# FMC_HPC1.net
KiCad netlist of a schematic drawn in Altium Designer
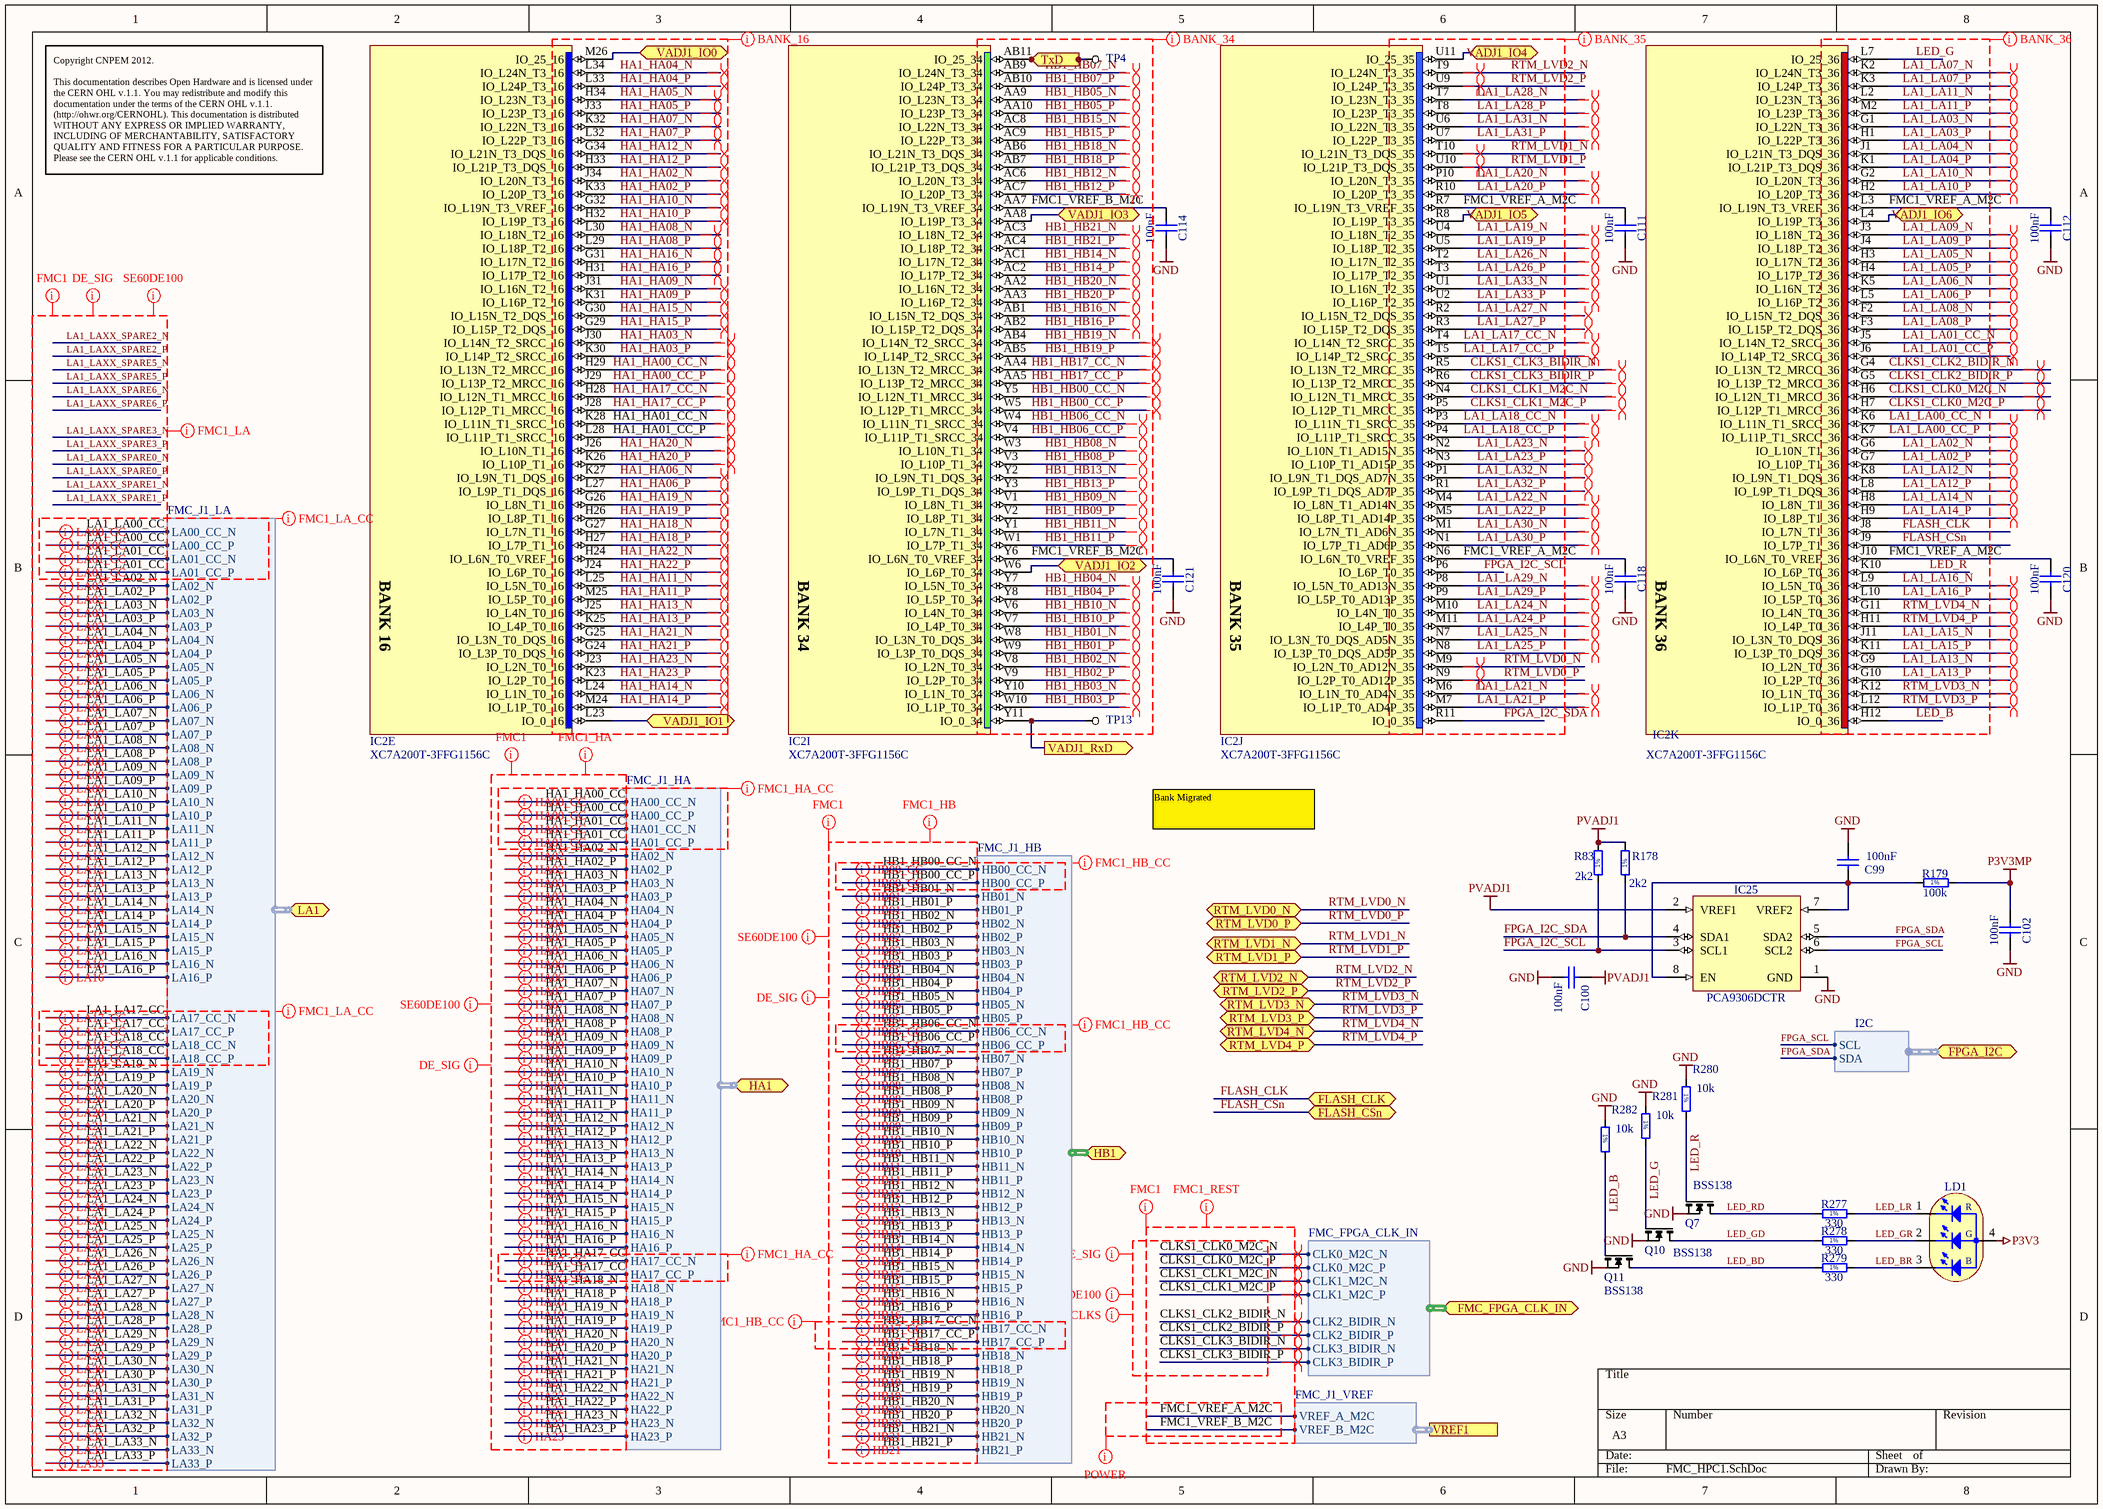
[diagram p0: FMC_HPC1.SchDoc]

(export (version "E")
  (design (tool "Eeschema 10.0.6"))
  (components
    (comp (ref "C99")
      (value "100nF")
      (footprint "CAPC0603X33N")
      (description "Non-polarised capacitor")
      (fields
        (field (name "PART NUMBER") "CC0201_100NF_6.3V_10%_X5R")
        (field (name "VOLTAGE") "6.3V")
        (field (name "AUTHOR") "CERN DEM JLC")
      )
      (libsource (lib "Capacitors") (part "Capacitor - non polarized"))
    )
    (comp (ref "C100")
      (value "100nF")
      (footprint "CAPC0603X33N")
      (description "Non-polarised capacitor")
      (fields
        (field (name "PART NUMBER") "CC0201_100NF_6.3V_10%_X5R")
        (field (name "VOLTAGE") "6.3V")
        (field (name "AUTHOR") "CERN DEM JLC")
      )
      (libsource (lib "Capacitors") (part "Capacitor - non polarized"))
    )
    (comp (ref "C102")
      (value "100nF")
      (footprint "CAPC0603X33N")
      (description "Non-polarised capacitor")
      (fields
        (field (name "PART NUMBER") "CC0201_100NF_6.3V_10%_X5R")
        (field (name "VOLTAGE") "6.3V")
        (field (name "AUTHOR") "CERN DEM JLC")
      )
      (libsource (lib "Capacitors") (part "Capacitor - non polarized"))
    )
    (comp (ref "C111")
      (value "100nF")
      (footprint "CAPC0603X33N")
      (description "Non-polarised capacitor")
      (fields
        (field (name "PART NUMBER") "CC0201_100NF_6.3V_10%_X5R")
        (field (name "VOLTAGE") "6.3V")
        (field (name "AUTHOR") "CERN DEM JLC")
      )
      (libsource (lib "Capacitors") (part "Capacitor - non polarized"))
    )
    (comp (ref "C112")
      (value "100nF")
      (footprint "CAPC0603X33N")
      (description "Non-polarised capacitor")
      (fields
        (field (name "PART NUMBER") "CC0201_100NF_6.3V_10%_X5R")
        (field (name "VOLTAGE") "6.3V")
        (field (name "AUTHOR") "CERN DEM JLC")
      )
      (libsource (lib "Capacitors") (part "Capacitor - non polarized"))
    )
    (comp (ref "C114")
      (value "100nF")
      (footprint "CAPC0603X33N")
      (description "Non-polarised capacitor")
      (fields
        (field (name "PART NUMBER") "CC0201_100NF_6.3V_10%_X5R")
        (field (name "VOLTAGE") "6.3V")
        (field (name "AUTHOR") "CERN DEM JLC")
      )
      (libsource (lib "Capacitors") (part "Capacitor - non polarized"))
    )
    (comp (ref "C118")
      (value "100nF")
      (footprint "CAPC0603X33N")
      (description "Non-polarised capacitor")
      (fields
        (field (name "PART NUMBER") "CC0201_100NF_6.3V_10%_X5R")
        (field (name "VOLTAGE") "6.3V")
        (field (name "AUTHOR") "CERN DEM JLC")
      )
      (libsource (lib "Capacitors") (part "Capacitor - non polarized"))
    )
    (comp (ref "C120")
      (value "100nF")
      (footprint "CAPC0603X33N")
      (description "Non-polarised capacitor")
      (fields
        (field (name "PART NUMBER") "CC0201_100NF_6.3V_10%_X5R")
        (field (name "VOLTAGE") "6.3V")
        (field (name "AUTHOR") "CERN DEM JLC")
      )
      (libsource (lib "Capacitors") (part "Capacitor - non polarized"))
    )
    (comp (ref "C121")
      (value "100nF")
      (footprint "CAPC0603X33N")
      (description "Non-polarised capacitor")
      (fields
        (field (name "PART NUMBER") "CC0201_100NF_6.3V_10%_X5R")
        (field (name "VOLTAGE") "6.3V")
        (field (name "AUTHOR") "CERN DEM JLC")
      )
      (libsource (lib "Capacitors") (part "Capacitor - non polarized"))
    )
    (comp (ref "IC2")
      (value "XC7A200T-3FFG1156C")
      (footprint "BGA1156C100P34X34_3500X3500X335")
      (description "Artix-6 FPGA, 16 GTPs, 600 User I/Os, 1156-Pin BGA, Speed Grade 2, Commercial Grade, Pb-Free")
      (fields (field (name "MANUFACTURER") "XILINX") (field (name "AUTHOR") "CERN DEM JLC"))
      (libsource (lib "AMC_FMC_Carrier") (part "XC7A200T-3FFG1156C"))
    )
    (comp (ref "IC25")
      (value "PCA9306DCTR")
      (footprint "SOP65P400X130-8N")
      (description "Dual Bidirectional I2C Bus And SMBus Voltage-Level Translator")
      (fields (field (name "MANUFACTURER") "TEXAS INSTRUMENTS") (field (name "AUTHOR") "CERN DEM JLC"))
      (libsource (lib "ICs And Semiconductors") (part "PCA9306DC"))
    )
    (comp (ref "LD1")
      (value "Red/Green/Blue")
      (footprint "LED_OPTEK_OVSRRGBCC3_a")
      (description "Right Angle Tricolor (RGB) Surface Mount LED, Body 3.2x1mm")
      (fields
        (field (name "PART NUMBER") "LED_OPTEK_OVSRRGBCC3_a")
        (field (name "MANUFACTURER") "OPTEK / TT ELECTRONICS")
        (field (name "AUTHOR") "CERN DEM JLC")
      )
      (libsource (lib "ICs And Semiconductors") (part "LED_OPTEK_OVSRRGBCC3"))
    )
    (comp (ref "Q7")
      (value "BSS138")
      (footprint "SOT95P251X112-3N")
      (libsource (lib "LIBRARY_SCH") (part "Q_BSS138"))
    )
    (comp (ref "Q10")
      (value "BSS138")
      (footprint "SOT95P251X112-3N")
      (libsource (lib "LIBRARY_SCH") (part "Q_BSS138"))
    )
    (comp (ref "Q11")
      (value "BSS138")
      (footprint "SOT95P251X112-3N")
      (libsource (lib "LIBRARY_SCH") (part "Q_BSS138"))
    )
    (comp (ref "R83")
      (value "2k2")
      (footprint "RESC1005X40N")
      (description "Resistor - 1%")
      (fields
        (field (name "PART NUMBER") "R0402_2K2_1%_0.0625W_100PPM")
        (field (name "POWER") "0.0625W")
        (field (name "AUTHOR") "CERN DEM JLC")
      )
      (libsource (lib "Resistors") (part "Resistor - 1%"))
    )
    (comp (ref "R178")
      (value "2k2")
      (footprint "RESC1005X40N")
      (description "Resistor - 1%")
      (fields
        (field (name "PART NUMBER") "R0402_2K2_1%_0.0625W_100PPM")
        (field (name "POWER") "0.0625W")
        (field (name "AUTHOR") "CERN DEM JLC")
      )
      (libsource (lib "Resistors") (part "Resistor - 1%"))
    )
    (comp (ref "R179")
      (value "100k")
      (footprint "RESC1005X40N")
      (description "Resistor - 1%")
      (fields
        (field (name "PART NUMBER") "R0402_100K_1%_0.0625W_100PPM")
        (field (name "POWER") "0.0625W")
        (field (name "AUTHOR") "CERN DEM JLC")
      )
      (libsource (lib "Resistors") (part "Resistor - 1%"))
    )
    (comp (ref "R277")
      (value "330")
      (footprint "RESC1005X40N")
      (description "Resistor - 1%")
      (fields
        (field (name "PART NUMBER") "R0402_330R_1%_0.0625W_100PPM")
        (field (name "POWER") "0.0625W")
        (field (name "AUTHOR") "CERN DEM JLC")
      )
      (libsource (lib "Resistors") (part "Resistor - 1%"))
    )
    (comp (ref "R278")
      (value "330")
      (footprint "RESC1005X40N")
      (description "Resistor - 1%")
      (fields
        (field (name "PART NUMBER") "R0402_330R_1%_0.0625W_100PPM")
        (field (name "POWER") "0.0625W")
        (field (name "AUTHOR") "CERN DEM JLC")
      )
      (libsource (lib "Resistors") (part "Resistor - 1%"))
    )
    (comp (ref "R279")
      (value "330")
      (footprint "RESC1005X40N")
      (description "Resistor - 1%")
      (fields
        (field (name "PART NUMBER") "R0402_330R_1%_0.0625W_100PPM")
        (field (name "POWER") "0.0625W")
        (field (name "AUTHOR") "CERN DEM JLC")
      )
      (libsource (lib "Resistors") (part "Resistor - 1%"))
    )
    (comp (ref "R280")
      (value "10k")
      (footprint "RESC1005X40N")
      (description "Resistor - 1%")
      (fields
        (field (name "PART NUMBER") "R0402_10K_1%_0.0625W_100PPM")
        (field (name "POWER") "0.0625W")
        (field (name "AUTHOR") "CERN DEM JLC")
      )
      (libsource (lib "Resistors") (part "Resistor - 1%"))
    )
    (comp (ref "R281")
      (value "10k")
      (footprint "RESC1005X40N")
      (description "Resistor - 1%")
      (fields
        (field (name "PART NUMBER") "R0402_10K_1%_0.0625W_100PPM")
        (field (name "POWER") "0.0625W")
        (field (name "AUTHOR") "CERN DEM JLC")
      )
      (libsource (lib "Resistors") (part "Resistor - 1%"))
    )
    (comp (ref "R282")
      (value "10k")
      (footprint "RESC1005X40N")
      (description "Resistor - 1%")
      (fields
        (field (name "PART NUMBER") "R0402_10K_1%_0.0625W_100PPM")
        (field (name "POWER") "0.0625W")
        (field (name "AUTHOR") "CERN DEM JLC")
      )
      (libsource (lib "Resistors") (part "Resistor - 1%"))
    )
    (comp (ref "TP4")
      (value "TP")
      (footprint "TP_large")
      (description "Testpoint")
      (libsource (lib "LIBRARY_SCH") (part "TP"))
    )
    (comp (ref "TP13")
      (value "TP")
      (footprint "TP_large")
      (description "Testpoint")
      (libsource (lib "LIBRARY_SCH") (part "TP"))
    )
  )
  (nets
    (net (code "7") (name "/CLKS1_CLK0_M2C_N") (class "Default")
      (node (ref "IC2") (pin "H6") (pinfunction "IO_L12N_T1_MRCC_36_H6") (pintype "bidirectional"))
    )
    (net (code "8") (name "/CLKS1_CLK0_M2C_P") (class "Default")
      (node (ref "IC2") (pin "H7") (pinfunction "IO_L12P_T1_MRCC_36_H7") (pintype "bidirectional"))
    )
    (net (code "9") (name "/CLKS1_CLK1_M2C_N") (class "Default")
      (node (ref "IC2") (pin "N4") (pinfunction "IO_L12N_T1_MRCC_35_N4") (pintype "bidirectional"))
    )
    (net (code "10") (name "/CLKS1_CLK1_M2C_P") (class "Default")
      (node (ref "IC2") (pin "P5") (pinfunction "IO_L12P_T1_MRCC_35_P5") (pintype "bidirectional"))
    )
    (net (code "11") (name "/CLKS1_CLK2_BIDIR_N") (class "Default")
      (node (ref "IC2") (pin "G4") (pinfunction "IO_L13N_T2_MRCC_36_G4") (pintype "bidirectional"))
    )
    (net (code "12") (name "/CLKS1_CLK2_BIDIR_P") (class "Default")
      (node (ref "IC2") (pin "G5") (pinfunction "IO_L13P_T2_MRCC_36_G5") (pintype "bidirectional"))
    )
    (net (code "13") (name "/CLKS1_CLK3_BIDIR_N") (class "Default")
      (node (ref "IC2") (pin "R5") (pinfunction "IO_L13N_T2_MRCC_35_R5") (pintype "bidirectional"))
    )
    (net (code "14") (name "/CLKS1_CLK3_BIDIR_P") (class "Default")
      (node (ref "IC2") (pin "R6") (pinfunction "IO_L13P_T2_MRCC_35_R6") (pintype "bidirectional"))
    )
    (net (code "15") (name "/FLASH_CLK") (class "Default")
      (node (ref "IC2") (pin "J8") (pinfunction "IO_L7N_T1_36_J8") (pintype "bidirectional"))
    )
    (net (code "16") (name "/FLASH_CSn") (class "Default")
      (node (ref "IC2") (pin "J9") (pinfunction "IO_L7P_T1_36_J9") (pintype "bidirectional"))
    )
    (net (code "17") (name "/FMC1_VREF_A_M2C") (class "Default")
      (node (ref "C111") (pin "1") (pinfunction "1_1") (pintype "passive"))
      (node (ref "C112") (pin "1") (pinfunction "1_1") (pintype "passive"))
      (node (ref "C118") (pin "1") (pinfunction "1_1") (pintype "passive"))
      (node (ref "C120") (pin "1") (pinfunction "1_1") (pintype "passive"))
      (node (ref "IC2") (pin "J10") (pinfunction "IO_L6N_T0_VREF_36_J10") (pintype "bidirectional"))
      (node (ref "IC2") (pin "L3") (pinfunction "IO_L19N_T3_VREF_36_L3") (pintype "bidirectional"))
      (node (ref "IC2") (pin "N6") (pinfunction "IO_L6N_T0_VREF_35_N6") (pintype "bidirectional"))
      (node (ref "IC2") (pin "R7") (pinfunction "IO_L19N_T3_VREF_35_R7") (pintype "bidirectional"))
    )
    (net (code "18") (name "/FMC1_VREF_B_M2C") (class "Default")
      (node (ref "C114") (pin "1") (pinfunction "1_1") (pintype "passive"))
      (node (ref "C121") (pin "1") (pinfunction "1_1") (pintype "passive"))
      (node (ref "IC2") (pin "AA7") (pinfunction "IO_L19N_T3_VREF_34_AA7") (pintype "bidirectional"))
      (node (ref "IC2") (pin "Y6") (pinfunction "IO_L6N_T0_VREF_34_Y6") (pintype "bidirectional"))
    )
    (net (code "19") (name "/FPGA_I2C_SCL") (class "Default")
      (node (ref "IC2") (pin "P6") (pinfunction "IO_L6P_T0_35_P6") (pintype "bidirectional"))
      (node (ref "IC25") (pin "3") (pinfunction "SCL1_3") (pintype "bidirectional"))
      (node (ref "R83") (pin "1") (pinfunction "1_1") (pintype "passive"))
    )
    (net (code "20") (name "/FPGA_I2C_SDA") (class "Default")
      (node (ref "IC2") (pin "R11") (pinfunction "IO_0_35_R11") (pintype "bidirectional"))
      (node (ref "IC25") (pin "4") (pinfunction "SDA1_4") (pintype "bidirectional"))
      (node (ref "R178") (pin "1") (pinfunction "1_1") (pintype "passive"))
    )
    (net (code "21") (name "/FPGA_SCL") (class "Default")
      (node (ref "IC25") (pin "6") (pinfunction "SCL2_6") (pintype "bidirectional"))
    )
    (net (code "22") (name "/FPGA_SDA") (class "Default")
      (node (ref "IC25") (pin "5") (pinfunction "SDA2_5") (pintype "bidirectional"))
    )
    (net (code "23") (name "/HA1_HA00_CC_N") (class "Default")
      (node (ref "IC2") (pin "H29") (pinfunction "IO_L13N_T2_MRCC_16_H29") (pintype "bidirectional"))
    )
    (net (code "24") (name "/HA1_HA00_CC_P") (class "Default")
      (node (ref "IC2") (pin "J29") (pinfunction "IO_L13P_T2_MRCC_16_J29") (pintype "bidirectional"))
    )
    (net (code "25") (name "/HA1_HA01_CC_N") (class "Default")
      (node (ref "IC2") (pin "K28") (pinfunction "IO_L11N_T1_SRCC_16_K28") (pintype "bidirectional"))
    )
    (net (code "26") (name "/HA1_HA01_CC_P") (class "Default")
      (node (ref "IC2") (pin "L28") (pinfunction "IO_L11P_T1_SRCC_16_L28") (pintype "bidirectional"))
    )
    (net (code "27") (name "/HA1_HA02_N") (class "Default")
      (node (ref "IC2") (pin "J34") (pinfunction "IO_L20N_T3_16_J34") (pintype "bidirectional"))
    )
    (net (code "28") (name "/HA1_HA02_P") (class "Default")
      (node (ref "IC2") (pin "K33") (pinfunction "IO_L20P_T3_16_K33") (pintype "bidirectional"))
    )
    (net (code "29") (name "/HA1_HA03_N") (class "Default")
      (node (ref "IC2") (pin "J30") (pinfunction "IO_L14N_T2_SRCC_16_J30") (pintype "bidirectional"))
    )
    (net (code "30") (name "/HA1_HA03_P") (class "Default")
      (node (ref "IC2") (pin "K30") (pinfunction "IO_L14P_T2_SRCC_16_K30") (pintype "bidirectional"))
    )
    (net (code "31") (name "/HA1_HA04_N") (class "Default")
      (node (ref "IC2") (pin "L34") (pinfunction "IO_L24N_T3_16_L34") (pintype "bidirectional"))
    )
    (net (code "32") (name "/HA1_HA04_P") (class "Default")
      (node (ref "IC2") (pin "L33") (pinfunction "IO_L24P_T3_16_L33") (pintype "bidirectional"))
    )
    (net (code "33") (name "/HA1_HA05_N") (class "Default")
      (node (ref "IC2") (pin "H34") (pinfunction "IO_L23N_T3_16_H34") (pintype "bidirectional"))
    )
    (net (code "34") (name "/HA1_HA05_P") (class "Default")
      (node (ref "IC2") (pin "J33") (pinfunction "IO_L23P_T3_16_J33") (pintype "bidirectional"))
    )
    (net (code "35") (name "/HA1_HA06_N") (class "Default")
      (node (ref "IC2") (pin "K27") (pinfunction "IO_L9N_T1_DQS_16_K27") (pintype "bidirectional"))
    )
    (net (code "36") (name "/HA1_HA06_P") (class "Default")
      (node (ref "IC2") (pin "L27") (pinfunction "IO_L9P_T1_DQS_16_L27") (pintype "bidirectional"))
    )
    (net (code "37") (name "/HA1_HA07_N") (class "Default")
      (node (ref "IC2") (pin "K32") (pinfunction "IO_L22N_T3_16_K32") (pintype "bidirectional"))
    )
    (net (code "38") (name "/HA1_HA07_P") (class "Default")
      (node (ref "IC2") (pin "L32") (pinfunction "IO_L22P_T3_16_L32") (pintype "bidirectional"))
    )
    (net (code "39") (name "/HA1_HA08_N") (class "Default")
      (node (ref "IC2") (pin "L30") (pinfunction "IO_L18N_T2_16_L30") (pintype "bidirectional"))
    )
    (net (code "40") (name "/HA1_HA08_P") (class "Default")
      (node (ref "IC2") (pin "L29") (pinfunction "IO_L18P_T2_16_L29") (pintype "bidirectional"))
    )
    (net (code "41") (name "/HA1_HA09_N") (class "Default")
      (node (ref "IC2") (pin "J31") (pinfunction "IO_L16N_T2_16_J31") (pintype "bidirectional"))
    )
    (net (code "42") (name "/HA1_HA09_P") (class "Default")
      (node (ref "IC2") (pin "K31") (pinfunction "IO_L16P_T2_16_K31") (pintype "bidirectional"))
    )
    (net (code "43") (name "/HA1_HA10_N") (class "Default")
      (node (ref "IC2") (pin "G32") (pinfunction "IO_L19N_T3_VREF_16_G32") (pintype "bidirectional"))
    )
    (net (code "44") (name "/HA1_HA10_P") (class "Default")
      (node (ref "IC2") (pin "H32") (pinfunction "IO_L19P_T3_16_H32") (pintype "bidirectional"))
    )
    (net (code "45") (name "/HA1_HA11_N") (class "Default")
      (node (ref "IC2") (pin "L25") (pinfunction "IO_L5N_T0_16_L25") (pintype "bidirectional"))
    )
    (net (code "46") (name "/HA1_HA11_P") (class "Default")
      (node (ref "IC2") (pin "M25") (pinfunction "IO_L5P_T0_16_M25") (pintype "bidirectional"))
    )
    (net (code "47") (name "/HA1_HA12_N") (class "Default")
      (node (ref "IC2") (pin "G34") (pinfunction "IO_L21N_T3_DQS_16_G34") (pintype "bidirectional"))
    )
    (net (code "48") (name "/HA1_HA12_P") (class "Default")
      (node (ref "IC2") (pin "H33") (pinfunction "IO_L21P_T3_DQS_16_H33") (pintype "bidirectional"))
    )
    (net (code "49") (name "/HA1_HA13_N") (class "Default")
      (node (ref "IC2") (pin "J25") (pinfunction "IO_L4N_T0_16_J25") (pintype "bidirectional"))
    )
    (net (code "50") (name "/HA1_HA13_P") (class "Default")
      (node (ref "IC2") (pin "K25") (pinfunction "IO_L4P_T0_16_K25") (pintype "bidirectional"))
    )
    (net (code "51") (name "/HA1_HA14_N") (class "Default")
      (node (ref "IC2") (pin "L24") (pinfunction "IO_L1N_T0_16_L24") (pintype "bidirectional"))
    )
    (net (code "52") (name "/HA1_HA14_P") (class "Default")
      (node (ref "IC2") (pin "M24") (pinfunction "IO_L1P_T0_16_M24") (pintype "bidirectional"))
    )
    (net (code "53") (name "/HA1_HA15_N") (class "Default")
      (node (ref "IC2") (pin "G30") (pinfunction "IO_L15N_T2_DQS_16_G30") (pintype "bidirectional"))
    )
    (net (code "54") (name "/HA1_HA15_P") (class "Default")
      (node (ref "IC2") (pin "G29") (pinfunction "IO_L15P_T2_DQS_16_G29") (pintype "bidirectional"))
    )
    (net (code "55") (name "/HA1_HA16_N") (class "Default")
      (node (ref "IC2") (pin "G31") (pinfunction "IO_L17N_T2_16_G31") (pintype "bidirectional"))
    )
    (net (code "56") (name "/HA1_HA16_P") (class "Default")
      (node (ref "IC2") (pin "H31") (pinfunction "IO_L17P_T2_16_H31") (pintype "bidirectional"))
    )
    (net (code "57") (name "/HA1_HA17_CC_N") (class "Default")
      (node (ref "IC2") (pin "H28") (pinfunction "IO_L12N_T1_MRCC_16_H28") (pintype "bidirectional"))
    )
    (net (code "58") (name "/HA1_HA17_CC_P") (class "Default")
      (node (ref "IC2") (pin "J28") (pinfunction "IO_L12P_T1_MRCC_16_J28") (pintype "bidirectional"))
    )
    (net (code "59") (name "/HA1_HA18_N") (class "Default")
      (node (ref "IC2") (pin "G27") (pinfunction "IO_L7N_T1_16_G27") (pintype "bidirectional"))
    )
    (net (code "60") (name "/HA1_HA18_P") (class "Default")
      (node (ref "IC2") (pin "H27") (pinfunction "IO_L7P_T1_16_H27") (pintype "bidirectional"))
    )
    (net (code "61") (name "/HA1_HA19_N") (class "Default")
      (node (ref "IC2") (pin "G26") (pinfunction "IO_L8N_T1_16_G26") (pintype "bidirectional"))
    )
    (net (code "62") (name "/HA1_HA19_P") (class "Default")
      (node (ref "IC2") (pin "H26") (pinfunction "IO_L8P_T1_16_H26") (pintype "bidirectional"))
    )
    (net (code "63") (name "/HA1_HA20_N") (class "Default")
      (node (ref "IC2") (pin "J26") (pinfunction "IO_L10N_T1_16_J26") (pintype "bidirectional"))
    )
    (net (code "64") (name "/HA1_HA20_P") (class "Default")
      (node (ref "IC2") (pin "K26") (pinfunction "IO_L10P_T1_16_K26") (pintype "bidirectional"))
    )
    (net (code "65") (name "/HA1_HA21_N") (class "Default")
      (node (ref "IC2") (pin "G25") (pinfunction "IO_L3N_T0_DQS_16_G25") (pintype "bidirectional"))
    )
    (net (code "66") (name "/HA1_HA21_P") (class "Default")
      (node (ref "IC2") (pin "G24") (pinfunction "IO_L3P_T0_DQS_16_G24") (pintype "bidirectional"))
    )
    (net (code "67") (name "/HA1_HA22_N") (class "Default")
      (node (ref "IC2") (pin "H24") (pinfunction "IO_L6N_T0_VREF_16_H24") (pintype "bidirectional"))
    )
    (net (code "68") (name "/HA1_HA22_P") (class "Default")
      (node (ref "IC2") (pin "J24") (pinfunction "IO_L6P_T0_16_J24") (pintype "bidirectional"))
    )
    (net (code "69") (name "/HA1_HA23_N") (class "Default")
      (node (ref "IC2") (pin "J23") (pinfunction "IO_L2N_T0_16_J23") (pintype "bidirectional"))
    )
    (net (code "70") (name "/HA1_HA23_P") (class "Default")
      (node (ref "IC2") (pin "K23") (pinfunction "IO_L2P_T0_16_K23") (pintype "bidirectional"))
    )
    (net (code "71") (name "/HB1_HB00_CC_N") (class "Default")
      (node (ref "IC2") (pin "Y5") (pinfunction "IO_L12N_T1_MRCC_34_Y5") (pintype "bidirectional"))
    )
    (net (code "72") (name "/HB1_HB00_CC_P") (class "Default")
      (node (ref "IC2") (pin "W5") (pinfunction "IO_L12P_T1_MRCC_34_W5") (pintype "bidirectional"))
    )
    (net (code "73") (name "/HB1_HB01_N") (class "Default")
      (node (ref "IC2") (pin "W8") (pinfunction "IO_L3N_T0_DQS_34_W8") (pintype "bidirectional"))
    )
    (net (code "74") (name "/HB1_HB01_P") (class "Default")
      (node (ref "IC2") (pin "W9") (pinfunction "IO_L3P_T0_DQS_34_W9") (pintype "bidirectional"))
    )
    (net (code "75") (name "/HB1_HB02_N") (class "Default")
      (node (ref "IC2") (pin "V8") (pinfunction "IO_L2N_T0_34_V8") (pintype "bidirectional"))
    )
    (net (code "76") (name "/HB1_HB02_P") (class "Default")
      (node (ref "IC2") (pin "V9") (pinfunction "IO_L2P_T0_34_V9") (pintype "bidirectional"))
    )
    (net (code "77") (name "/HB1_HB03_N") (class "Default")
      (node (ref "IC2") (pin "Y10") (pinfunction "IO_L1N_T0_34_Y10") (pintype "bidirectional"))
    )
    (net (code "78") (name "/HB1_HB03_P") (class "Default")
      (node (ref "IC2") (pin "W10") (pinfunction "IO_L1P_T0_34_W10") (pintype "bidirectional"))
    )
    (net (code "79") (name "/HB1_HB04_N") (class "Default")
      (node (ref "IC2") (pin "Y7") (pinfunction "IO_L5N_T0_34_Y7") (pintype "bidirectional"))
    )
    (net (code "80") (name "/HB1_HB04_P") (class "Default")
      (node (ref "IC2") (pin "Y8") (pinfunction "IO_L5P_T0_34_Y8") (pintype "bidirectional"))
    )
    (net (code "81") (name "/HB1_HB05_N") (class "Default")
      (node (ref "IC2") (pin "AA9") (pinfunction "IO_L23N_T3_34_AA9") (pintype "bidirectional"))
    )
    (net (code "82") (name "/HB1_HB05_P") (class "Default")
      (node (ref "IC2") (pin "AA10") (pinfunction "IO_L23P_T3_34_AA10") (pintype "bidirectional"))
    )
    (net (code "83") (name "/HB1_HB06_CC_N") (class "Default")
      (node (ref "IC2") (pin "W4") (pinfunction "IO_L11N_T1_SRCC_34_W4") (pintype "bidirectional"))
    )
    (net (code "84") (name "/HB1_HB06_CC_P") (class "Default")
      (node (ref "IC2") (pin "V4") (pinfunction "IO_L11P_T1_SRCC_34_V4") (pintype "bidirectional"))
    )
    (net (code "85") (name "/HB1_HB07_N") (class "Default")
      (node (ref "IC2") (pin "AB9") (pinfunction "IO_L24N_T3_34_AB9") (pintype "bidirectional"))
    )
    (net (code "86") (name "/HB1_HB07_P") (class "Default")
      (node (ref "IC2") (pin "AB10") (pinfunction "IO_L24P_T3_34_AB10") (pintype "bidirectional"))
    )
    (net (code "87") (name "/HB1_HB08_N") (class "Default")
      (node (ref "IC2") (pin "W3") (pinfunction "IO_L10N_T1_34_W3") (pintype "bidirectional"))
    )
    (net (code "88") (name "/HB1_HB08_P") (class "Default")
      (node (ref "IC2") (pin "V3") (pinfunction "IO_L10P_T1_34_V3") (pintype "bidirectional"))
    )
    (net (code "89") (name "/HB1_HB09_N") (class "Default")
      (node (ref "IC2") (pin "V1") (pinfunction "IO_L8N_T1_34_V1") (pintype "bidirectional"))
    )
    (net (code "90") (name "/HB1_HB09_P") (class "Default")
      (node (ref "IC2") (pin "V2") (pinfunction "IO_L8P_T1_34_V2") (pintype "bidirectional"))
    )
    (net (code "91") (name "/HB1_HB10_N") (class "Default")
      (node (ref "IC2") (pin "V6") (pinfunction "IO_L4N_T0_34_V6") (pintype "bidirectional"))
    )
    (net (code "92") (name "/HB1_HB10_P") (class "Default")
      (node (ref "IC2") (pin "V7") (pinfunction "IO_L4P_T0_34_V7") (pintype "bidirectional"))
    )
    (net (code "93") (name "/HB1_HB11_N") (class "Default")
      (node (ref "IC2") (pin "Y1") (pinfunction "IO_L7N_T1_34_Y1") (pintype "bidirectional"))
    )
    (net (code "94") (name "/HB1_HB11_P") (class "Default")
      (node (ref "IC2") (pin "W1") (pinfunction "IO_L7P_T1_34_W1") (pintype "bidirectional"))
    )
    (net (code "95") (name "/HB1_HB12_N") (class "Default")
      (node (ref "IC2") (pin "AC6") (pinfunction "IO_L20N_T3_34_AC6") (pintype "bidirectional"))
    )
    (net (code "96") (name "/HB1_HB12_P") (class "Default")
      (node (ref "IC2") (pin "AC7") (pinfunction "IO_L20P_T3_34_AC7") (pintype "bidirectional"))
    )
    (net (code "97") (name "/HB1_HB13_N") (class "Default")
      (node (ref "IC2") (pin "Y2") (pinfunction "IO_L9N_T1_DQS_34_Y2") (pintype "bidirectional"))
    )
    (net (code "98") (name "/HB1_HB13_P") (class "Default")
      (node (ref "IC2") (pin "Y3") (pinfunction "IO_L9P_T1_DQS_34_Y3") (pintype "bidirectional"))
    )
    (net (code "99") (name "/HB1_HB14_N") (class "Default")
      (node (ref "IC2") (pin "AC1") (pinfunction "IO_L17N_T2_34_AC1") (pintype "bidirectional"))
    )
    (net (code "100") (name "/HB1_HB14_P") (class "Default")
      (node (ref "IC2") (pin "AC2") (pinfunction "IO_L17P_T2_34_AC2") (pintype "bidirectional"))
    )
    (net (code "101") (name "/HB1_HB15_N") (class "Default")
      (node (ref "IC2") (pin "AC8") (pinfunction "IO_L22N_T3_34_AC8") (pintype "bidirectional"))
    )
    (net (code "102") (name "/HB1_HB15_P") (class "Default")
      (node (ref "IC2") (pin "AC9") (pinfunction "IO_L22P_T3_34_AC9") (pintype "bidirectional"))
    )
    (net (code "103") (name "/HB1_HB16_N") (class "Default")
      (node (ref "IC2") (pin "AB1") (pinfunction "IO_L15N_T2_DQS_34_AB1") (pintype "bidirectional"))
    )
    (net (code "104") (name "/HB1_HB16_P") (class "Default")
      (node (ref "IC2") (pin "AB2") (pinfunction "IO_L15P_T2_DQS_34_AB2") (pintype "bidirectional"))
    )
    (net (code "105") (name "/HB1_HB17_CC_N") (class "Default")
      (node (ref "IC2") (pin "AA4") (pinfunction "IO_L13N_T2_MRCC_34_AA4") (pintype "bidirectional"))
    )
    (net (code "106") (name "/HB1_HB17_CC_P") (class "Default")
      (node (ref "IC2") (pin "AA5") (pinfunction "IO_L13P_T2_MRCC_34_AA5") (pintype "bidirectional"))
    )
    (net (code "107") (name "/HB1_HB18_N") (class "Default")
      (node (ref "IC2") (pin "AB6") (pinfunction "IO_L21N_T3_DQS_34_AB6") (pintype "bidirectional"))
    )
    (net (code "108") (name "/HB1_HB18_P") (class "Default")
      (node (ref "IC2") (pin "AB7") (pinfunction "IO_L21P_T3_DQS_34_AB7") (pintype "bidirectional"))
    )
    (net (code "109") (name "/HB1_HB19_N") (class "Default")
      (node (ref "IC2") (pin "AB4") (pinfunction "IO_L14N_T2_SRCC_34_AB4") (pintype "bidirectional"))
    )
    (net (code "110") (name "/HB1_HB19_P") (class "Default")
      (node (ref "IC2") (pin "AB5") (pinfunction "IO_L14P_T2_SRCC_34_AB5") (pintype "bidirectional"))
    )
    (net (code "111") (name "/HB1_HB20_N") (class "Default")
      (node (ref "IC2") (pin "AA2") (pinfunction "IO_L16N_T2_34_AA2") (pintype "bidirectional"))
    )
    (net (code "112") (name "/HB1_HB20_P") (class "Default")
      (node (ref "IC2") (pin "AA3") (pinfunction "IO_L16P_T2_34_AA3") (pintype "bidirectional"))
    )
    (net (code "113") (name "/HB1_HB21_N") (class "Default")
      (node (ref "IC2") (pin "AC3") (pinfunction "IO_L18N_T2_34_AC3") (pintype "bidirectional"))
    )
    (net (code "114") (name "/HB1_HB21_P") (class "Default")
      (node (ref "IC2") (pin "AC4") (pinfunction "IO_L18P_T2_34_AC4") (pintype "bidirectional"))
    )
    (net (code "115") (name "/LA1_LA00_CC_N") (class "Default")
      (node (ref "IC2") (pin "K6") (pinfunction "IO_L11N_T1_SRCC_36_K6") (pintype "bidirectional"))
    )
    (net (code "116") (name "/LA1_LA00_CC_P") (class "Default")
      (node (ref "IC2") (pin "K7") (pinfunction "IO_L11P_T1_SRCC_36_K7") (pintype "bidirectional"))
    )
    (net (code "117") (name "/LA1_LA01_CC_N") (class "Default")
      (node (ref "IC2") (pin "J5") (pinfunction "IO_L14N_T2_SRCC_36_J5") (pintype "bidirectional"))
    )
    (net (code "118") (name "/LA1_LA01_CC_P") (class "Default")
      (node (ref "IC2") (pin "J6") (pinfunction "IO_L14P_T2_SRCC_36_J6") (pintype "bidirectional"))
    )
    (net (code "119") (name "/LA1_LA02_N") (class "Default")
      (node (ref "IC2") (pin "G6") (pinfunction "IO_L10N_T1_36_G6") (pintype "bidirectional"))
    )
    (net (code "120") (name "/LA1_LA02_P") (class "Default")
      (node (ref "IC2") (pin "G7") (pinfunction "IO_L10P_T1_36_G7") (pintype "bidirectional"))
    )
    (net (code "121") (name "/LA1_LA03_N") (class "Default")
      (node (ref "IC2") (pin "G1") (pinfunction "IO_L22N_T3_36_G1") (pintype "bidirectional"))
    )
    (net (code "122") (name "/LA1_LA03_P") (class "Default")
      (node (ref "IC2") (pin "H1") (pinfunction "IO_L22P_T3_36_H1") (pintype "bidirectional"))
    )
    (net (code "123") (name "/LA1_LA04_N") (class "Default")
      (node (ref "IC2") (pin "J1") (pinfunction "IO_L21N_T3_DQS_36_J1") (pintype "bidirectional"))
    )
    (net (code "124") (name "/LA1_LA04_P") (class "Default")
      (node (ref "IC2") (pin "K1") (pinfunction "IO_L21P_T3_DQS_36_K1") (pintype "bidirectional"))
    )
    (net (code "125") (name "/LA1_LA05_N") (class "Default")
      (node (ref "IC2") (pin "H3") (pinfunction "IO_L17N_T2_36_H3") (pintype "bidirectional"))
    )
    (net (code "126") (name "/LA1_LA05_P") (class "Default")
      (node (ref "IC2") (pin "H4") (pinfunction "IO_L17P_T2_36_H4") (pintype "bidirectional"))
    )
    (net (code "127") (name "/LA1_LA06_N") (class "Default")
      (node (ref "IC2") (pin "K5") (pinfunction "IO_L16N_T2_36_K5") (pintype "bidirectional"))
    )
    (net (code "128") (name "/LA1_LA06_P") (class "Default")
      (node (ref "IC2") (pin "L5") (pinfunction "IO_L16P_T2_36_L5") (pintype "bidirectional"))
    )
    (net (code "129") (name "/LA1_LA07_N") (class "Default")
      (node (ref "IC2") (pin "K2") (pinfunction "IO_L24N_T3_36_K2") (pintype "bidirectional"))
    )
    (net (code "130") (name "/LA1_LA07_P") (class "Default")
      (node (ref "IC2") (pin "K3") (pinfunction "IO_L24P_T3_36_K3") (pintype "bidirectional"))
    )
    (net (code "131") (name "/LA1_LA08_N") (class "Default")
      (node (ref "IC2") (pin "F2") (pinfunction "IO_L15N_T2_DQS_36_F2") (pintype "bidirectional"))
    )
    (net (code "132") (name "/LA1_LA08_P") (class "Default")
      (node (ref "IC2") (pin "F3") (pinfunction "IO_L15P_T2_DQS_36_F3") (pintype "bidirectional"))
    )
    (net (code "133") (name "/LA1_LA09_N") (class "Default")
      (node (ref "IC2") (pin "J3") (pinfunction "IO_L18N_T2_36_J3") (pintype "bidirectional"))
    )
    (net (code "134") (name "/LA1_LA09_P") (class "Default")
      (node (ref "IC2") (pin "J4") (pinfunction "IO_L18P_T2_36_J4") (pintype "bidirectional"))
    )
    (net (code "135") (name "/LA1_LA10_N") (class "Default")
      (node (ref "IC2") (pin "G2") (pinfunction "IO_L20N_T3_36_G2") (pintype "bidirectional"))
    )
    (net (code "136") (name "/LA1_LA10_P") (class "Default")
      (node (ref "IC2") (pin "H2") (pinfunction "IO_L20P_T3_36_H2") (pintype "bidirectional"))
    )
    (net (code "137") (name "/LA1_LA11_N") (class "Default")
      (node (ref "IC2") (pin "L2") (pinfunction "IO_L23N_T3_36_L2") (pintype "bidirectional"))
    )
    (net (code "138") (name "/LA1_LA11_P") (class "Default")
      (node (ref "IC2") (pin "M2") (pinfunction "IO_L23P_T3_36_M2") (pintype "bidirectional"))
    )
    (net (code "139") (name "/LA1_LA12_N") (class "Default")
      (node (ref "IC2") (pin "K8") (pinfunction "IO_L9N_T1_DQS_36_K8") (pintype "bidirectional"))
    )
    (net (code "140") (name "/LA1_LA12_P") (class "Default")
      (node (ref "IC2") (pin "L8") (pinfunction "IO_L9P_T1_DQS_36_L8") (pintype "bidirectional"))
    )
    (net (code "141") (name "/LA1_LA13_N") (class "Default")
      (node (ref "IC2") (pin "G9") (pinfunction "IO_L2N_T0_36_G9") (pintype "bidirectional"))
    )
    (net (code "142") (name "/LA1_LA13_P") (class "Default")
      (node (ref "IC2") (pin "G10") (pinfunction "IO_L2P_T0_36_G10") (pintype "bidirectional"))
    )
    (net (code "143") (name "/LA1_LA14_N") (class "Default")
      (node (ref "IC2") (pin "H8") (pinfunction "IO_L8N_T1_36_H8") (pintype "bidirectional"))
    )
    (net (code "144") (name "/LA1_LA14_P") (class "Default")
      (node (ref "IC2") (pin "H9") (pinfunction "IO_L8P_T1_36_H9") (pintype "bidirectional"))
    )
    (net (code "145") (name "/LA1_LA15_N") (class "Default")
      (node (ref "IC2") (pin "J11") (pinfunction "IO_L3N_T0_DQS_36_J11") (pintype "bidirectional"))
    )
    (net (code "146") (name "/LA1_LA15_P") (class "Default")
      (node (ref "IC2") (pin "K11") (pinfunction "IO_L3P_T0_DQS_36_K11") (pintype "bidirectional"))
    )
    (net (code "147") (name "/LA1_LA16_N") (class "Default")
      (node (ref "IC2") (pin "L9") (pinfunction "IO_L5N_T0_36_L9") (pintype "bidirectional"))
    )
    (net (code "148") (name "/LA1_LA16_P") (class "Default")
      (node (ref "IC2") (pin "L10") (pinfunction "IO_L5P_T0_36_L10") (pintype "bidirectional"))
    )
    (net (code "149") (name "/LA1_LA17_CC_N") (class "Default")
      (node (ref "IC2") (pin "T4") (pinfunction "IO_L14N_T2_SRCC_35_T4") (pintype "bidirectional"))
    )
    (net (code "150") (name "/LA1_LA17_CC_P") (class "Default")
      (node (ref "IC2") (pin "T5") (pinfunction "IO_L14P_T2_SRCC_35_T5") (pintype "bidirectional"))
    )
    (net (code "151") (name "/LA1_LA18_CC_N") (class "Default")
      (node (ref "IC2") (pin "P3") (pinfunction "IO_L11N_T1_SRCC_35_P3") (pintype "bidirectional"))
    )
    (net (code "152") (name "/LA1_LA18_CC_P") (class "Default")
      (node (ref "IC2") (pin "P4") (pinfunction "IO_L11P_T1_SRCC_35_P4") (pintype "bidirectional"))
    )
    (net (code "153") (name "/LA1_LA19_N") (class "Default")
      (node (ref "IC2") (pin "U4") (pinfunction "IO_L18N_T2_35_U4") (pintype "bidirectional"))
    )
    (net (code "154") (name "/LA1_LA19_P") (class "Default")
      (node (ref "IC2") (pin "U5") (pinfunction "IO_L18P_T2_35_U5") (pintype "bidirectional"))
    )
    (net (code "155") (name "/LA1_LA20_N") (class "Default")
      (node (ref "IC2") (pin "P10") (pinfunction "IO_L20N_T3_35_P10") (pintype "bidirectional"))
    )
    (net (code "156") (name "/LA1_LA20_P") (class "Default")
      (node (ref "IC2") (pin "R10") (pinfunction "IO_L20P_T3_35_R10") (pintype "bidirectional"))
    )
    (net (code "157") (name "/LA1_LA21_N") (class "Default")
      (node (ref "IC2") (pin "M6") (pinfunction "IO_L1N_T0_AD4N_35_M6") (pintype "bidirectional"))
    )
    (net (code "158") (name "/LA1_LA21_P") (class "Default")
      (node (ref "IC2") (pin "M7") (pinfunction "IO_L1P_T0_AD4P_35_M7") (pintype "bidirectional"))
    )
    (net (code "159") (name "/LA1_LA22_N") (class "Default")
      (node (ref "IC2") (pin "M4") (pinfunction "IO_L8N_T1_AD14N_35_M4") (pintype "bidirectional"))
    )
    (net (code "160") (name "/LA1_LA22_P") (class "Default")
      (node (ref "IC2") (pin "M5") (pinfunction "IO_L8P_T1_AD14P_35_M5") (pintype "bidirectional"))
    )
    (net (code "161") (name "/LA1_LA23_N") (class "Default")
      (node (ref "IC2") (pin "N2") (pinfunction "IO_L10N_T1_AD15N_35_N2") (pintype "bidirectional"))
    )
    (net (code "162") (name "/LA1_LA23_P") (class "Default")
      (node (ref "IC2") (pin "N3") (pinfunction "IO_L10P_T1_AD15P_35_N3") (pintype "bidirectional"))
    )
    (net (code "163") (name "/LA1_LA24_N") (class "Default")
      (node (ref "IC2") (pin "M10") (pinfunction "IO_L4N_T0_35_M10") (pintype "bidirectional"))
    )
    (net (code "164") (name "/LA1_LA24_P") (class "Default")
      (node (ref "IC2") (pin "M11") (pinfunction "IO_L4P_T0_35_M11") (pintype "bidirectional"))
    )
    (net (code "165") (name "/LA1_LA25_N") (class "Default")
      (node (ref "IC2") (pin "N7") (pinfunction "IO_L3N_T0_DQS_AD5N_35_N7") (pintype "bidirectional"))
    )
    (net (code "166") (name "/LA1_LA25_P") (class "Default")
      (node (ref "IC2") (pin "N8") (pinfunction "IO_L3P_T0_DQS_AD5P_35_N8") (pintype "bidirectional"))
    )
    (net (code "167") (name "/LA1_LA26_N") (class "Default")
      (node (ref "IC2") (pin "T2") (pinfunction "IO_L17N_T2_35_T2") (pintype "bidirectional"))
    )
    (net (code "168") (name "/LA1_LA26_P") (class "Default")
      (node (ref "IC2") (pin "T3") (pinfunction "IO_L17P_T2_35_T3") (pintype "bidirectional"))
    )
    (net (code "169") (name "/LA1_LA27_N") (class "Default")
      (node (ref "IC2") (pin "R2") (pinfunction "IO_L15N_T2_DQS_35_R2") (pintype "bidirectional"))
    )
    (net (code "170") (name "/LA1_LA27_P") (class "Default")
      (node (ref "IC2") (pin "R3") (pinfunction "IO_L15P_T2_DQS_35_R3") (pintype "bidirectional"))
    )
    (net (code "171") (name "/LA1_LA28_N") (class "Default")
      (node (ref "IC2") (pin "T7") (pinfunction "IO_L23N_T3_35_T7") (pintype "bidirectional"))
    )
    (net (code "172") (name "/LA1_LA28_P") (class "Default")
      (node (ref "IC2") (pin "T8") (pinfunction "IO_L23P_T3_35_T8") (pintype "bidirectional"))
    )
    (net (code "173") (name "/LA1_LA29_N") (class "Default")
      (node (ref "IC2") (pin "P8") (pinfunction "IO_L5N_T0_AD13N_35_P8") (pintype "bidirectional"))
    )
    (net (code "174") (name "/LA1_LA29_P") (class "Default")
      (node (ref "IC2") (pin "P9") (pinfunction "IO_L5P_T0_AD13P_35_P9") (pintype "bidirectional"))
    )
    (net (code "175") (name "/LA1_LA30_N") (class "Default")
      (node (ref "IC2") (pin "M1") (pinfunction "IO_L7N_T1_AD6N_35_M1") (pintype "bidirectional"))
    )
    (net (code "176") (name "/LA1_LA30_P") (class "Default")
      (node (ref "IC2") (pin "N1") (pinfunction "IO_L7P_T1_AD6P_35_N1") (pintype "bidirectional"))
    )
    (net (code "177") (name "/LA1_LA31_N") (class "Default")
      (node (ref "IC2") (pin "U6") (pinfunction "IO_L22N_T3_35_U6") (pintype "bidirectional"))
    )
    (net (code "178") (name "/LA1_LA31_P") (class "Default")
      (node (ref "IC2") (pin "U7") (pinfunction "IO_L22P_T3_35_U7") (pintype "bidirectional"))
    )
    (net (code "179") (name "/LA1_LA32_N") (class "Default")
      (node (ref "IC2") (pin "P1") (pinfunction "IO_L9N_T1_DQS_AD7N_35_P1") (pintype "bidirectional"))
    )
    (net (code "180") (name "/LA1_LA32_P") (class "Default")
      (node (ref "IC2") (pin "R1") (pinfunction "IO_L9P_T1_DQS_AD7P_35_R1") (pintype "bidirectional"))
    )
    (net (code "181") (name "/LA1_LA33_N") (class "Default")
      (node (ref "IC2") (pin "U1") (pinfunction "IO_L16N_T2_35_U1") (pintype "bidirectional"))
    )
    (net (code "182") (name "/LA1_LA33_P") (class "Default")
      (node (ref "IC2") (pin "U2") (pinfunction "IO_L16P_T2_35_U2") (pintype "bidirectional"))
    )
    (net (code "195") (name "/LED_B") (class "Default")
      (node (ref "IC2") (pin "H12") (pinfunction "IO_0_36_H12") (pintype "bidirectional"))
      (node (ref "Q11") (pin "1") (pinfunction "G_1") (pintype "input"))
      (node (ref "R282") (pin "2") (pinfunction "2_2") (pintype "passive"))
    )
    (net (code "196") (name "/LED_BD") (class "Default")
      (node (ref "Q11") (pin "3") (pinfunction "D_3") (pintype "passive"))
      (node (ref "R279") (pin "1") (pinfunction "1_1") (pintype "passive"))
    )
    (net (code "197") (name "/LED_BR") (class "Default")
      (node (ref "LD1") (pin "3") (pinfunction "AB_3") (pintype "passive"))
      (node (ref "R279") (pin "2") (pinfunction "2_2") (pintype "passive"))
    )
    (net (code "198") (name "/LED_G") (class "Default")
      (node (ref "IC2") (pin "L7") (pinfunction "IO_25_36_L7") (pintype "bidirectional"))
      (node (ref "Q10") (pin "1") (pinfunction "G_1") (pintype "input"))
      (node (ref "R281") (pin "2") (pinfunction "2_2") (pintype "passive"))
    )
    (net (code "199") (name "/LED_GD") (class "Default")
      (node (ref "Q10") (pin "3") (pinfunction "D_3") (pintype "passive"))
      (node (ref "R278") (pin "1") (pinfunction "1_1") (pintype "passive"))
    )
    (net (code "200") (name "/LED_GR") (class "Default")
      (node (ref "LD1") (pin "2") (pinfunction "AG_2") (pintype "passive"))
      (node (ref "R278") (pin "2") (pinfunction "2_2") (pintype "passive"))
    )
    (net (code "201") (name "/LED_LR") (class "Default")
      (node (ref "LD1") (pin "1") (pinfunction "AR_1") (pintype "passive"))
      (node (ref "R277") (pin "2") (pinfunction "2_2") (pintype "passive"))
    )
    (net (code "202") (name "/LED_R") (class "Default")
      (node (ref "IC2") (pin "K10") (pinfunction "IO_L6P_T0_36_K10") (pintype "bidirectional"))
      (node (ref "Q7") (pin "1") (pinfunction "G_1") (pintype "input"))
      (node (ref "R280") (pin "2") (pinfunction "2_2") (pintype "passive"))
    )
    (net (code "203") (name "/LED_RD") (class "Default")
      (node (ref "Q7") (pin "3") (pinfunction "D_3") (pintype "passive"))
      (node (ref "R277") (pin "1") (pinfunction "1_1") (pintype "passive"))
    )
    (net (code "204") (name "/RTM_LVD0_N") (class "Default")
      (node (ref "IC2") (pin "M9") (pinfunction "IO_L2N_T0_AD12N_35_M9") (pintype "bidirectional"))
    )
    (net (code "205") (name "/RTM_LVD0_P") (class "Default")
      (node (ref "IC2") (pin "N9") (pinfunction "IO_L2P_T0_AD12P_35_N9") (pintype "bidirectional"))
    )
    (net (code "206") (name "/RTM_LVD1_N") (class "Default")
      (node (ref "IC2") (pin "T10") (pinfunction "IO_L21N_T3_DQS_35_T10") (pintype "bidirectional"))
    )
    (net (code "207") (name "/RTM_LVD1_P") (class "Default")
      (node (ref "IC2") (pin "U10") (pinfunction "IO_L21P_T3_DQS_35_U10") (pintype "bidirectional"))
    )
    (net (code "208") (name "/RTM_LVD2_N") (class "Default")
      (node (ref "IC2") (pin "T9") (pinfunction "IO_L24N_T3_35_T9") (pintype "bidirectional"))
    )
    (net (code "209") (name "/RTM_LVD2_P") (class "Default")
      (node (ref "IC2") (pin "U9") (pinfunction "IO_L24P_T3_35_U9") (pintype "bidirectional"))
    )
    (net (code "210") (name "/RTM_LVD3_N") (class "Default")
      (node (ref "IC2") (pin "K12") (pinfunction "IO_L1N_T0_36_K12") (pintype "bidirectional"))
    )
    (net (code "211") (name "/RTM_LVD3_P") (class "Default")
      (node (ref "IC2") (pin "L12") (pinfunction "IO_L1P_T0_36_L12") (pintype "bidirectional"))
    )
    (net (code "212") (name "/RTM_LVD4_N") (class "Default")
      (node (ref "IC2") (pin "G11") (pinfunction "IO_L4N_T0_36_G11") (pintype "bidirectional"))
    )
    (net (code "213") (name "/RTM_LVD4_P") (class "Default")
      (node (ref "IC2") (pin "H11") (pinfunction "IO_L4P_T0_36_H11") (pintype "bidirectional"))
    )
    (net (code "214") (name "/TxD") (class "Default")
      (node (ref "IC2") (pin "AB11") (pinfunction "IO_25_34_AB11") (pintype "bidirectional"))
      (node (ref "TP4") (pin "1") (pintype "passive"))
    )
    (net (code "215") (name "/VADJ1_IO0") (class "Default")
      (node (ref "IC2") (pin "M26") (pinfunction "IO_25_16_M26") (pintype "bidirectional"))
    )
    (net (code "216") (name "/VADJ1_IO1") (class "Default")
      (node (ref "IC2") (pin "L23") (pinfunction "IO_0_16_L23") (pintype "bidirectional"))
    )
    (net (code "217") (name "/VADJ1_IO2") (class "Default")
      (node (ref "IC2") (pin "W6") (pinfunction "IO_L6P_T0_34_W6") (pintype "bidirectional"))
    )
    (net (code "218") (name "/VADJ1_IO3") (class "Default")
      (node (ref "IC2") (pin "AA8") (pinfunction "IO_L19P_T3_34_AA8") (pintype "bidirectional"))
    )
    (net (code "219") (name "/VADJ1_IO4") (class "Default")
      (node (ref "IC2") (pin "U11") (pinfunction "IO_25_35_U11") (pintype "bidirectional"))
    )
    (net (code "220") (name "/VADJ1_IO5") (class "Default")
      (node (ref "IC2") (pin "R8") (pinfunction "IO_L19P_T3_35_R8") (pintype "bidirectional"))
    )
    (net (code "221") (name "/VADJ1_IO6") (class "Default")
      (node (ref "IC2") (pin "L4") (pinfunction "IO_L19P_T3_36_L4") (pintype "bidirectional"))
    )
    (net (code "222") (name "/VADJ1_RxD") (class "Default")
      (node (ref "IC2") (pin "Y11") (pinfunction "IO_0_34_Y11") (pintype "bidirectional"))
      (node (ref "TP13") (pin "1") (pintype "passive"))
    )
    (net (code "229") (name "GND") (class "Default")
      (node (ref "C100") (pin "2") (pinfunction "2_2") (pintype "passive"))
      (node (ref "C102") (pin "2") (pinfunction "2_2") (pintype "passive"))
      (node (ref "C111") (pin "2") (pinfunction "2_2") (pintype "passive"))
      (node (ref "C112") (pin "2") (pinfunction "2_2") (pintype "passive"))
      (node (ref "C114") (pin "2") (pinfunction "2_2") (pintype "passive"))
      (node (ref "C118") (pin "2") (pinfunction "2_2") (pintype "passive"))
      (node (ref "C120") (pin "2") (pinfunction "2_2") (pintype "passive"))
      (node (ref "C121") (pin "2") (pinfunction "2_2") (pintype "passive"))
      (node (ref "C99") (pin "2") (pinfunction "2_2") (pintype "passive"))
      (node (ref "IC25") (pin "1") (pinfunction "GND_1") (pintype "power_in"))
      (node (ref "Q10") (pin "2") (pinfunction "S_2") (pintype "passive"))
      (node (ref "Q11") (pin "2") (pinfunction "S_2") (pintype "passive"))
      (node (ref "Q7") (pin "2") (pinfunction "S_2") (pintype "passive"))
      (node (ref "R280") (pin "1") (pinfunction "1_1") (pintype "passive"))
      (node (ref "R281") (pin "1") (pinfunction "1_1") (pintype "passive"))
      (node (ref "R282") (pin "1") (pinfunction "1_1") (pintype "passive"))
    )
    (net (code "230") (name "Net-(IC25-EN)") (class "Default")
      (node (ref "C99") (pin "1") (pinfunction "1_1") (pintype "passive"))
      (node (ref "IC25") (pin "7") (pinfunction "VREF2_7") (pintype "input"))
      (node (ref "IC25") (pin "8") (pinfunction "EN_8") (pintype "input"))
      (node (ref "R179") (pin "1") (pinfunction "1_1") (pintype "passive"))
    )
    (net (code "231") (name "P3V3") (class "Default")
      (node (ref "LD1") (pin "4") (pinfunction "CC_4") (pintype "passive"))
    )
    (net (code "232") (name "P3V3MP") (class "Default")
      (node (ref "C102") (pin "1") (pinfunction "1_1") (pintype "passive"))
      (node (ref "R179") (pin "2") (pinfunction "2_2") (pintype "passive"))
    )
    (net (code "233") (name "PVADJ1") (class "Default")
      (node (ref "C100") (pin "1") (pinfunction "1_1") (pintype "passive"))
      (node (ref "IC25") (pin "2") (pinfunction "VREF1_2") (pintype "input"))
      (node (ref "R178") (pin "2") (pinfunction "2_2") (pintype "passive"))
      (node (ref "R83") (pin "2") (pinfunction "2_2") (pintype "passive"))
    )
  )
)
